# MB1297_POWER.net
KiCad netlist of a schematic drawn in Altium Designer
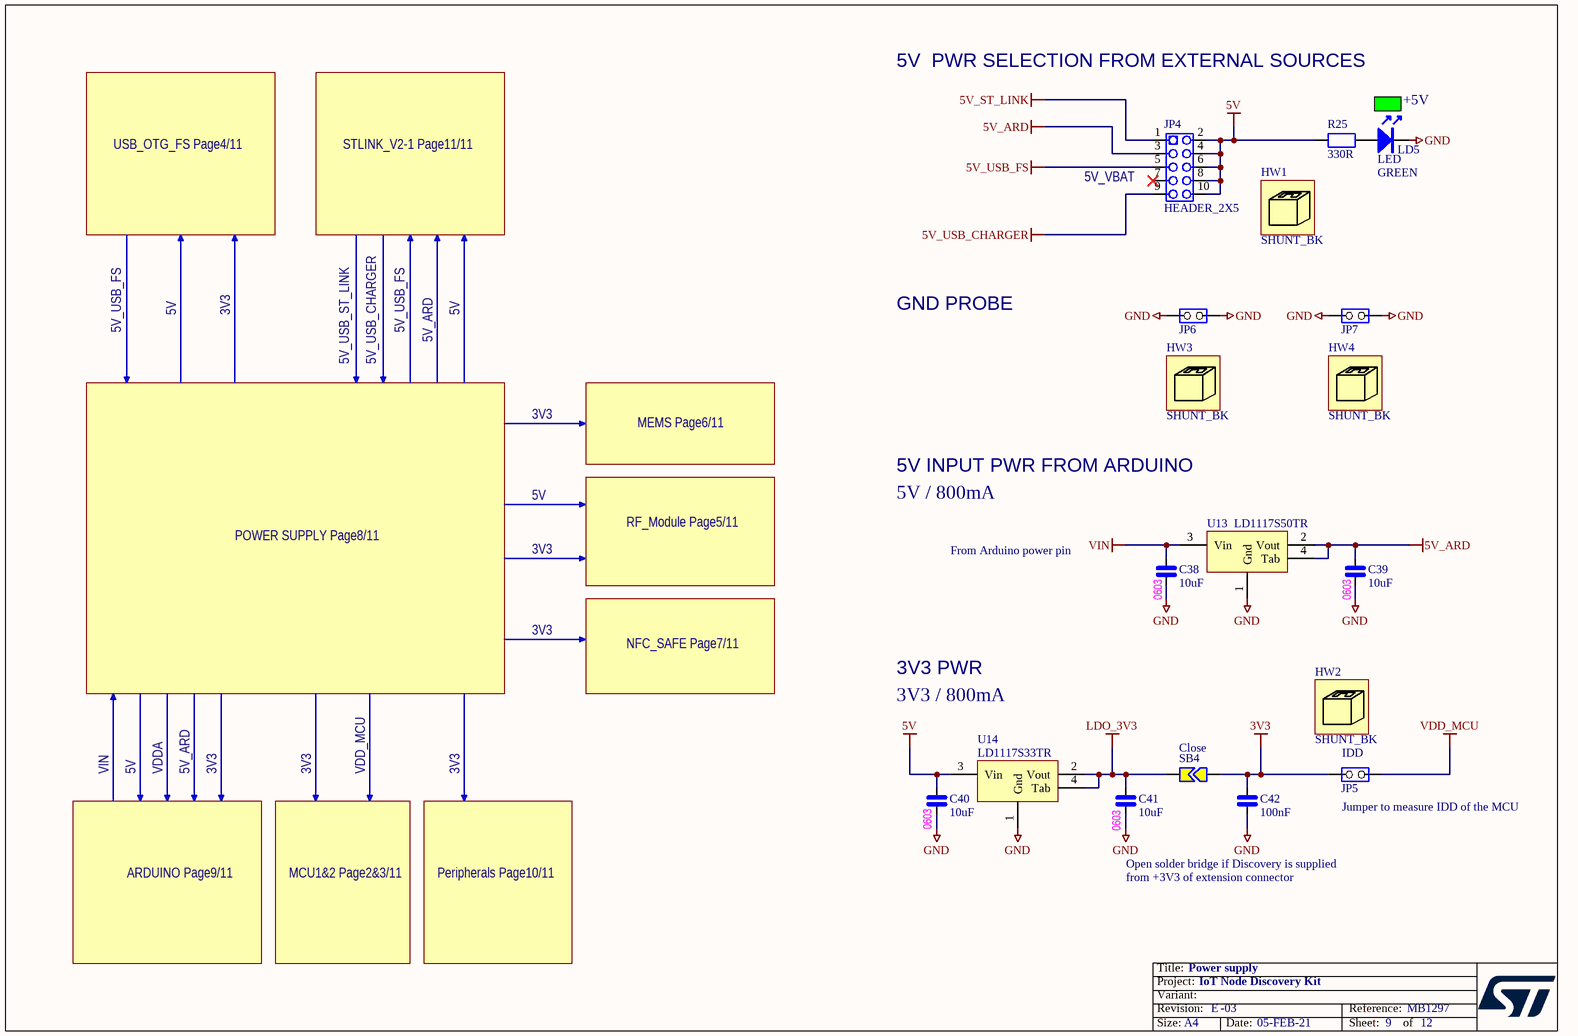
[diagram p0: MB1297_POWER.SchDoc]

(export (version "E")
  (design (tool "Eeschema 10.0.6"))
  (components
    (comp (ref "C38")
      (value "10uF")
      (footprint "0603_CAP_NPOL")
      (description "Capacitor_not polarized")
      (libsource (lib "ST_Lib3D") (part "CAP_NPOL"))
    )
    (comp (ref "C39")
      (value "10uF")
      (footprint "0603_CAP_NPOL")
      (description "Capacitor_not polarized")
      (libsource (lib "ST_Lib3D") (part "CAP_NPOL"))
    )
    (comp (ref "C40")
      (value "10uF")
      (footprint "0603_CAP_NPOL")
      (description "Capacitor_not polarized")
      (libsource (lib "ST_Lib3D") (part "CAP_NPOL"))
    )
    (comp (ref "C41")
      (value "10uF")
      (footprint "0603_CAP_NPOL")
      (description "Capacitor_not polarized")
      (libsource (lib "ST_Lib3D") (part "CAP_NPOL"))
    )
    (comp (ref "C42")
      (value "100nF")
      (footprint "0402")
      (description "Capacitor_not polarized")
      (libsource (lib "ST_Lib3D") (part "CAP_NPOL"))
    )
    (comp (ref "HW1")
      (value "SHUNT_BK")
      (description "SHUNT 2.54mm BLACK")
      (libsource (lib "MCD_TEMP_PCH") (part "Shunt 2.54mm"))
    )
    (comp (ref "HW2")
      (value "SHUNT_BK")
      (description "SHUNT 2.54mm BLACK")
      (libsource (lib "MCD_TEMP_PCH") (part "Shunt 2.54mm"))
    )
    (comp (ref "HW3")
      (value "SHUNT_BK")
      (description "SHUNT 2.54mm BLACK")
      (libsource (lib "MCD_TEMP_PCH") (part "Shunt 2.54mm"))
    )
    (comp (ref "HW4")
      (value "SHUNT_BK")
      (description "SHUNT 2.54mm BLACK")
      (libsource (lib "MCD_TEMP_PCH") (part "Shunt 2.54mm"))
    )
    (comp (ref "JP4")
      (value "HEADER_2X5")
      (footprint "Header M 2x5x2.54 TH V")
      (libsource (lib "ST_Lib3D") (part "HEADER_2X5"))
    )
    (comp (ref "JP5")
      (value "Jumper_2.54mm")
      (footprint "CON_SAMTEC_TSW-102-07-G-S")
      (description "Connector jumper 1 position")
      (libsource (lib "MCD_TEMP_PCH") (part "TSW-102-07-x-S"))
    )
    (comp (ref "JP6")
      (value "Jumper_2.54mm")
      (footprint "CON_SAMTEC_TSW-102-07-G-S")
      (description "Connector jumper 1 position")
      (libsource (lib "MCD_TEMP_PCH") (part "TSW-102-07-x-S"))
    )
    (comp (ref "JP7")
      (value "Jumper_2.54mm")
      (footprint "CON_SAMTEC_TSW-102-07-G-S")
      (description "Connector jumper 1 position")
      (libsource (lib "MCD_TEMP_PCH") (part "TSW-102-07-x-S"))
    )
    (comp (ref "LD5")
      (value "LED")
      (footprint "0603_LED_GREEN")
      (description "Light-Emitting Diode")
      (fields (field (name "COLOR") "GREEN"))
      (libsource (lib "ST_Lib3D") (part "LED"))
    )
    (comp (ref "R25")
      (value "330R")
      (footprint "0402")
      (description "Resistor")
      (libsource (lib "Lib3D_Altium10_Schlib") (part "RES"))
    )
    (comp (ref "SB4")
      (value "Close")
      (footprint "SB")
      (description "Solder Jumper")
      (fields (field (name "PUBLISHER") "Altium Limited"))
      (libsource (lib "Lib3D_Altium10_Schlib") (part "Strap2"))
    )
    (comp (ref "U13")
      (value "LD1117S50TR")
      (footprint "REG_SOT223-TAB")
      (description "IC REG LDO 5V 0.8A SOT223")
      (libsource (lib "MCD_TEMP_PCH") (part "LD1117S50TR"))
    )
    (comp (ref "U14")
      (value "LD1117S33TR")
      (footprint "REG_SOT223-TAB")
      (description "LOW DROP FIXED AND ADJUSTABLE POSITIVE VOLTAGE REGULATORS (3.3 Volts)")
      (libsource (lib "MCD_TEMP_PCH") (part "LD1117S33TR"))
    )
  )
  (nets
    (net (code "1") (name "3V3") (class "Default")
      (node (ref "C42") (pin "1") (pinfunction "1_1") (pintype "passive"))
      (node (ref "JP5") (pin "1") (pinfunction "COMMON_1") (pintype "passive"))
      (node (ref "SB4") (pin "2") (pinfunction "2_2") (pintype "passive"))
    )
    (net (code "2") (name "5V") (class "Default")
      (node (ref "C40") (pin "1") (pinfunction "1_1") (pintype "passive"))
      (node (ref "JP4") (pin "10") (pinfunction "10_10") (pintype "passive"))
      (node (ref "JP4") (pin "2") (pinfunction "2_2") (pintype "passive"))
      (node (ref "JP4") (pin "4") (pinfunction "4_4") (pintype "passive"))
      (node (ref "JP4") (pin "6") (pinfunction "6_6") (pintype "passive"))
      (node (ref "JP4") (pin "8") (pinfunction "8_8") (pintype "passive"))
      (node (ref "R25") (pin "1") (pinfunction "1_1") (pintype "passive"))
      (node (ref "U14") (pin "3") (pinfunction "Vin_3") (pintype "passive"))
    )
    (net (code "3") (name "5V_ARD") (class "Default")
      (node (ref "C39") (pin "1") (pinfunction "1_1") (pintype "passive"))
      (node (ref "JP4") (pin "3") (pinfunction "3_3") (pintype "passive"))
      (node (ref "U13") (pin "2") (pinfunction "Vout_2") (pintype "passive"))
      (node (ref "U13") (pin "4") (pinfunction "Tab_4") (pintype "passive"))
    )
    (net (code "4") (name "5V_ST_LINK") (class "Default")
      (node (ref "JP4") (pin "1") (pinfunction "1_1") (pintype "passive"))
    )
    (net (code "5") (name "5V_USB_CHARGER") (class "Default")
      (node (ref "JP4") (pin "9") (pinfunction "9_9") (pintype "passive"))
    )
    (net (code "6") (name "5V_USB_FS") (class "Default")
      (node (ref "JP4") (pin "5") (pinfunction "5_5") (pintype "passive"))
    )
    (net (code "7") (name "GND") (class "Default")
      (node (ref "C38") (pin "2") (pinfunction "2_2") (pintype "passive"))
      (node (ref "C39") (pin "2") (pinfunction "2_2") (pintype "passive"))
      (node (ref "C40") (pin "2") (pinfunction "2_2") (pintype "passive"))
      (node (ref "C41") (pin "2") (pinfunction "2_2") (pintype "passive"))
      (node (ref "C42") (pin "2") (pinfunction "2_2") (pintype "passive"))
      (node (ref "JP6") (pin "1") (pinfunction "COMMON_1") (pintype "passive"))
      (node (ref "JP6") (pin "2") (pinfunction "NO_2") (pintype "passive"))
      (node (ref "JP7") (pin "1") (pinfunction "COMMON_1") (pintype "passive"))
      (node (ref "JP7") (pin "2") (pinfunction "NO_2") (pintype "passive"))
      (node (ref "LD5") (pin "K") (pinfunction "K_K") (pintype "passive"))
      (node (ref "U13") (pin "1") (pinfunction "Gnd_1") (pintype "passive"))
      (node (ref "U14") (pin "1") (pinfunction "Gnd_1") (pintype "passive"))
    )
    (net (code "8") (name "LDO_3V3") (class "Default")
      (node (ref "C41") (pin "1") (pinfunction "1_1") (pintype "passive"))
      (node (ref "SB4") (pin "1") (pinfunction "1_1") (pintype "passive"))
      (node (ref "U14") (pin "2") (pinfunction "Vout_2") (pintype "passive"))
      (node (ref "U14") (pin "4") (pinfunction "Tab_4") (pintype "passive"))
    )
    (net (code "9") (name "Net-(LD5-PadA)") (class "Default")
      (node (ref "LD5") (pin "A") (pinfunction "A_A") (pintype "passive"))
      (node (ref "R25") (pin "2") (pinfunction "2_2") (pintype "passive"))
    )
    (net (code "10") (name "VDD_MCU") (class "Default")
      (node (ref "JP5") (pin "2") (pinfunction "NO_2") (pintype "passive"))
    )
    (net (code "11") (name "VIN") (class "Default")
      (node (ref "C38") (pin "1") (pinfunction "1_1") (pintype "passive"))
      (node (ref "U13") (pin "3") (pinfunction "Vin_3") (pintype "passive"))
    )
    (net (code "12") (name "unconnected-(JP4-Pad7)") (class "Default")
      (node (ref "JP4") (pin "7") (pinfunction "7_7") (pintype "passive+no_connect"))
    )
  )
)
